# Odessa_Add_el.net
KiCad netlist of a schematic drawn in EAGLE
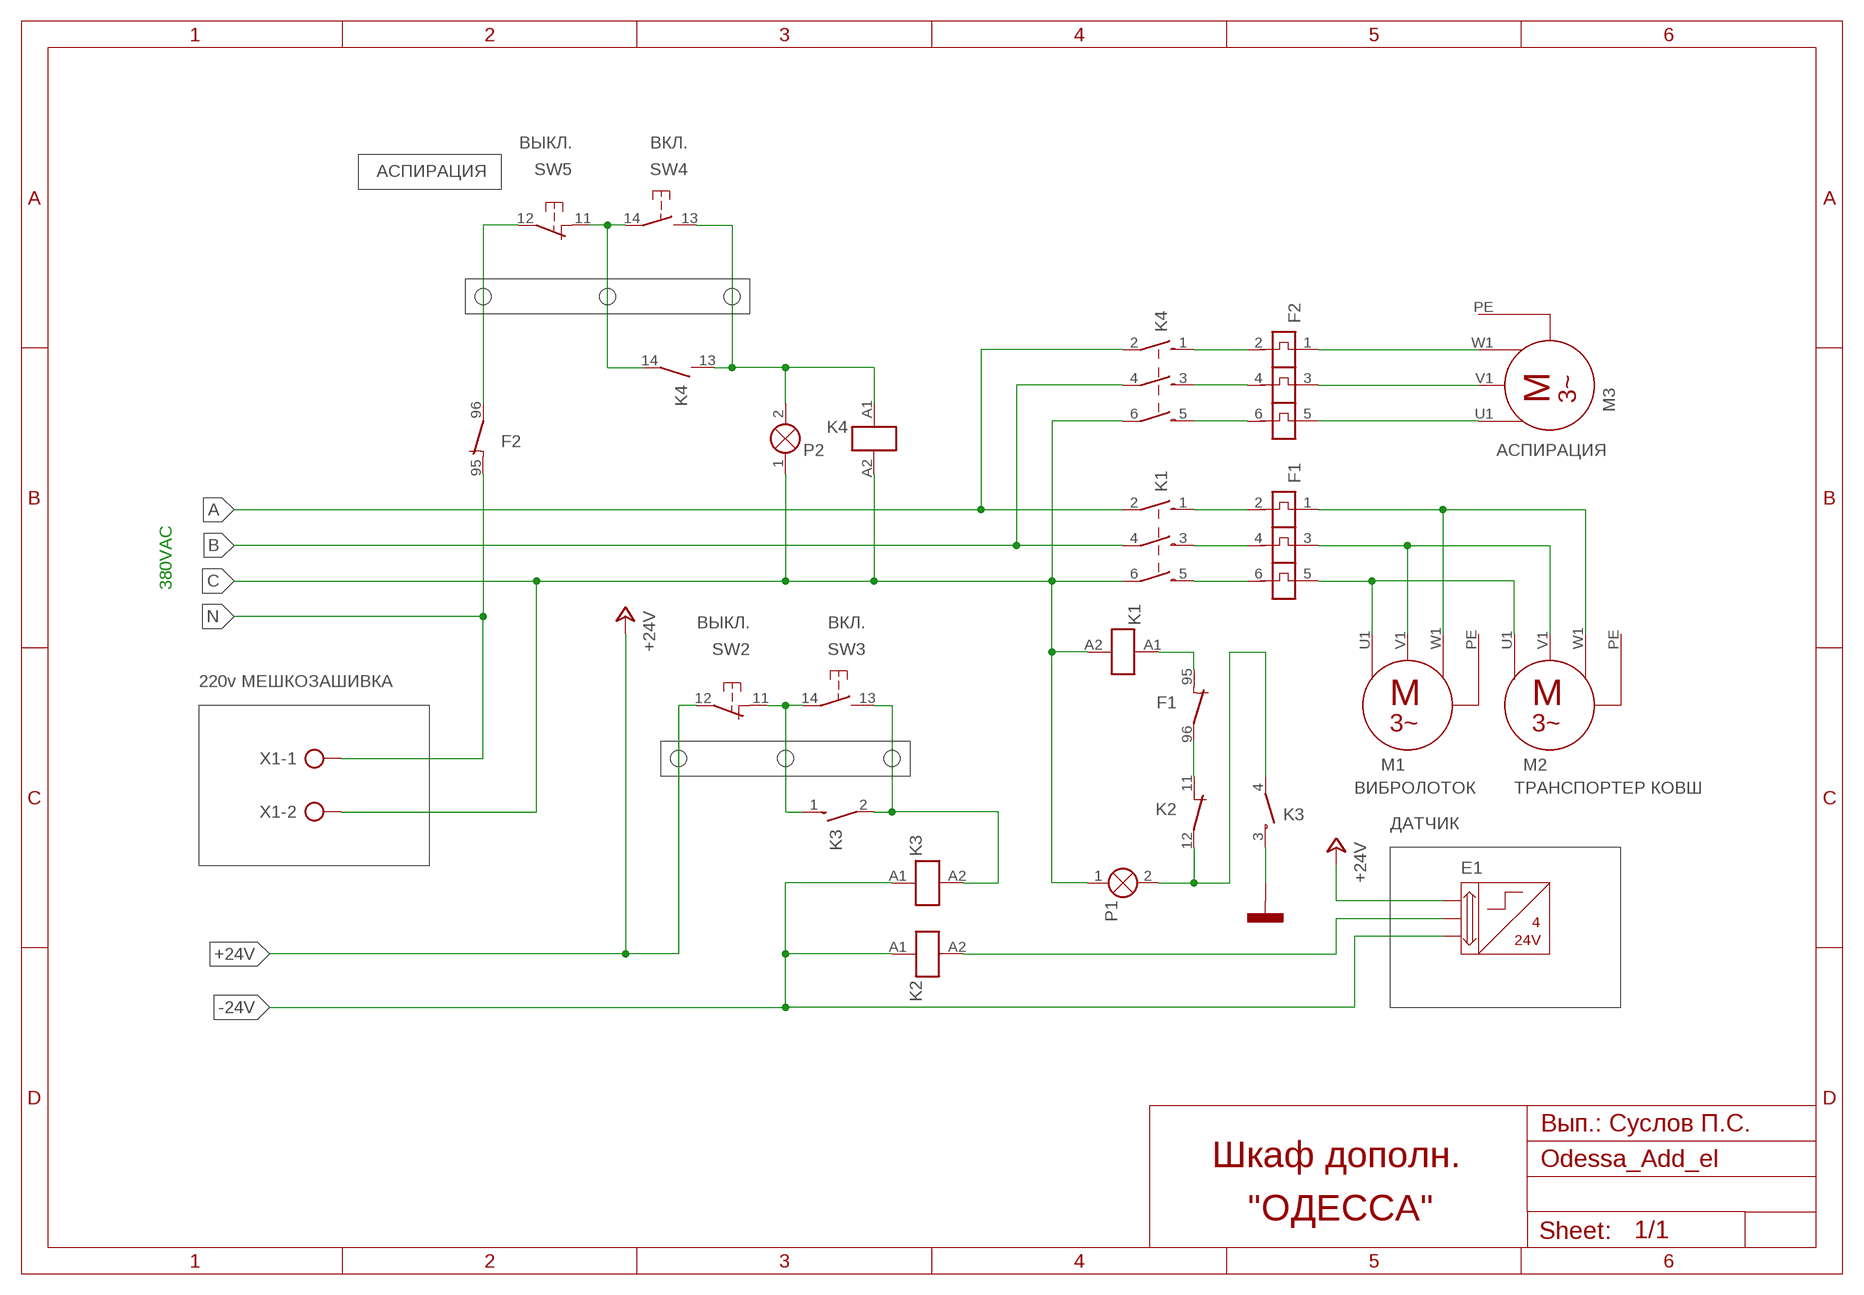
[diagram p0: schematic, sheet 1]

(export (version "E")
  (design (tool "Eeschema 10.0.6"))
  (components
    (comp (ref "E1")
      (value "6158EB")
      (footprint "eagle-import:6158EB")
      (libsource (lib "eagle-import") (part "6158EB"))
    )
    (comp (ref "F1")
      (value "MOTORSCHUTZSCHALTER_3-POL_THERM_AUSLOESUNG_HILFSKONTAKTE")
      (footprint "eagle-import:MOTORSCHUTZSCHALTER_3-POL_THERM_AUSLOESUNG_HILFSKONTAKT_95_96_97_98")
      (libsource (lib "eagle-import") (part "MOTORSCHUTZSCHALTER_3-POL_THERM_AUSLOESUNG_HILFSKONTAKTE"))
    )
    (comp (ref "F2")
      (value "MOTORSCHUTZSCHALTER_3-POL_THERM_AUSLOESUNG_HILFSKONTAKTE")
      (footprint "eagle-import:MOTORSCHUTZSCHALTER_3-POL_THERM_AUSLOESUNG_HILFSKONTAKT_95_96_97_98")
      (libsource (lib "eagle-import") (part "MOTORSCHUTZSCHALTER_3-POL_THERM_AUSLOESUNG_HILFSKONTAKTE"))
    )
    (comp (ref "K1")
      (value "HAUPTSCHUETZ_3-POL")
      (footprint "eagle-import:HAUPTSCHUETZ_3-POL")
      (libsource (lib "eagle-import") (part "HAUPTSCHUETZ_3-POL"))
    )
    (comp (ref "K2")
      (value "HILFSSCHUETZ_11-12")
      (footprint "eagle-import:HILFSSCHUETZ_11-12")
      (libsource (lib "eagle-import") (part "HILFSSCHUETZ_11-12"))
    )
    (comp (ref "K3")
      (value "HAUPTSCHUETZ_2-POL")
      (footprint "eagle-import:HAUPTSCHUETZ_2-POL")
      (libsource (lib "eagle-import") (part "HAUPTSCHUETZ_2-POL"))
    )
    (comp (ref "K4")
      (value "HAUPTSCHUETZ_3-POL_HILFSKONTAKT_13-14")
      (footprint "eagle-import:HAUPTSCHUETZ_3-POL+HILFSKONTAKT_13-14")
      (libsource (lib "eagle-import") (part "HAUPTSCHUETZ_3-POL_HILFSKONTAKT_13-14"))
    )
    (comp (ref "M1")
      (value "MOTOR_3-POL_PE")
      (footprint "eagle-import:MOTOR_3-POL_PE")
      (libsource (lib "eagle-import") (part "MOTOR_3-POL_PE"))
    )
    (comp (ref "M2")
      (value "MOTOR_3-POL_PE")
      (footprint "eagle-import:MOTOR_3-POL_PE")
      (libsource (lib "eagle-import") (part "MOTOR_3-POL_PE"))
    )
    (comp (ref "M3")
      (value "MOTOR_3-POL_PE")
      (footprint "eagle-import:MOTOR_3-POL_PE")
      (libsource (lib "eagle-import") (part "MOTOR_3-POL_PE"))
    )
    (comp (ref "P1")
      (value "SIGNALLAMPE")
      (footprint "eagle-import:LAMPE")
      (libsource (lib "eagle-import") (part "SIGNALLAMPE"))
    )
    (comp (ref "P2")
      (value "SIGNALLAMPE")
      (footprint "eagle-import:LAMPE")
      (libsource (lib "eagle-import") (part "SIGNALLAMPE"))
    )
    (comp (ref "SW2")
      (value "ВЫКЛ.")
      (footprint "eagle-import:OEFFNER_TASTSCHALTER")
      (libsource (lib "eagle-import") (part "OEFFNER_TASTSCHALTER"))
    )
    (comp (ref "SW3")
      (value "ВКЛ.")
      (footprint "eagle-import:SCHLIESSER_TASTSCHALTER")
      (libsource (lib "eagle-import") (part "SCHLIESSER_TASTSCHALTER"))
    )
    (comp (ref "SW4")
      (value "ВКЛ.")
      (footprint "eagle-import:SCHLIESSER_TASTSCHALTER")
      (libsource (lib "eagle-import") (part "SCHLIESSER_TASTSCHALTER"))
    )
    (comp (ref "SW5")
      (value "ВЫКЛ.")
      (footprint "eagle-import:OEFFNER_TASTSCHALTER")
      (libsource (lib "eagle-import") (part "OEFFNER_TASTSCHALTER"))
    )
    (comp (ref "X1")
      (value "AK500/2")
      (footprint "eagle-import:AK500_2")
      (libsource (lib "eagle-import") (part "AK500/2"))
    )
    (comp (ref "X4")
      (value "MASSE_ALLGEMEIN")
      (footprint "eagle-import:MASSE_ALLGEMEIN")
      (libsource (lib "eagle-import") (part "MASSE_ALLGEMEIN"))
    )
  )
  (nets
    (net (code "1") (name "+24V") (class "Default")
      (node (ref "SW2") (pin "12") (pinfunction "2_12") (pintype "input"))
    )
    (net (code "2") (name "-24V") (class "Default")
      (node (ref "K2") (pin "A1") (pinfunction "A1_A1") (pintype "input"))
      (node (ref "K3") (pin "A1") (pinfunction "A1_A1") (pintype "input"))
    )
    (net (code "3") (name "A") (class "Default")
      (node (ref "K1") (pin "2") (pinfunction "2_2") (pintype "passive"))
      (node (ref "K4") (pin "2") (pinfunction "2_2") (pintype "passive"))
    )
    (net (code "4") (name "B") (class "Default")
      (node (ref "K1") (pin "4") (pinfunction "4_4") (pintype "passive"))
      (node (ref "K4") (pin "4") (pinfunction "4_4") (pintype "passive"))
    )
    (net (code "5") (name "C") (class "Default")
      (node (ref "K1") (pin "6") (pinfunction "6_6") (pintype "passive"))
      (node (ref "K1") (pin "A2") (pinfunction "A2_A2") (pintype "input"))
      (node (ref "K4") (pin "6") (pinfunction "6_6") (pintype "passive"))
      (node (ref "K4") (pin "A2") (pinfunction "A2_A2") (pintype "input"))
      (node (ref "P1") (pin "1") (pinfunction "X1_1") (pintype "passive"))
      (node (ref "P2") (pin "1") (pinfunction "X1_1") (pintype "passive"))
      (node (ref "X1") (pin "2") (pinfunction "KL_2") (pintype "passive"))
    )
    (net (code "6") (name "N") (class "Default")
      (node (ref "F2") (pin "95") (pinfunction "95_95") (pintype "passive"))
      (node (ref "X1") (pin "1") (pinfunction "KL_1") (pintype "passive"))
    )
    (net (code "7") (name "Net-(E1-Pad1)") (class "Default")
      (node (ref "E1") (pin "1") (pinfunction "1_1") (pintype "passive"))
      (node (ref "K2") (pin "A2") (pinfunction "A2_A2") (pintype "input"))
    )
    (net (code "8") (name "Net-(F1-Pad1)") (class "Default")
      (node (ref "F1") (pin "1") (pinfunction "1_1") (pintype "passive"))
      (node (ref "M1") (pin "W1") (pinfunction "W1_W1") (pintype "passive"))
      (node (ref "M2") (pin "W1") (pinfunction "W1_W1") (pintype "passive"))
    )
    (net (code "9") (name "Net-(F1-Pad2)") (class "Default")
      (node (ref "F1") (pin "2") (pinfunction "2_2") (pintype "passive"))
      (node (ref "K1") (pin "1") (pinfunction "1_1") (pintype "passive"))
    )
    (net (code "10") (name "Net-(F1-Pad3)") (class "Default")
      (node (ref "F1") (pin "3") (pinfunction "3_3") (pintype "passive"))
      (node (ref "M1") (pin "V1") (pinfunction "V1_V1") (pintype "passive"))
      (node (ref "M2") (pin "V1") (pinfunction "V1_V1") (pintype "passive"))
    )
    (net (code "11") (name "Net-(F1-Pad4)") (class "Default")
      (node (ref "F1") (pin "4") (pinfunction "4_4") (pintype "passive"))
      (node (ref "K1") (pin "3") (pinfunction "3_3") (pintype "passive"))
    )
    (net (code "12") (name "Net-(F1-Pad5)") (class "Default")
      (node (ref "F1") (pin "5") (pinfunction "5_5") (pintype "passive"))
      (node (ref "M1") (pin "U1") (pinfunction "U1_U1") (pintype "passive"))
      (node (ref "M2") (pin "U1") (pinfunction "U1_U1") (pintype "passive"))
    )
    (net (code "13") (name "Net-(F1-Pad6)") (class "Default")
      (node (ref "F1") (pin "6") (pinfunction "6_6") (pintype "passive"))
      (node (ref "K1") (pin "5") (pinfunction "5_5") (pintype "passive"))
    )
    (net (code "14") (name "Net-(F1-Pad95)") (class "Default")
      (node (ref "F1") (pin "95") (pinfunction "95_95") (pintype "passive"))
      (node (ref "K1") (pin "A1") (pinfunction "A1_A1") (pintype "input"))
    )
    (net (code "15") (name "Net-(F2-Pad1)") (class "Default")
      (node (ref "F2") (pin "1") (pinfunction "1_1") (pintype "passive"))
      (node (ref "M3") (pin "W1") (pinfunction "W1_W1") (pintype "passive"))
    )
    (net (code "16") (name "Net-(F2-Pad2)") (class "Default")
      (node (ref "F2") (pin "2") (pinfunction "2_2") (pintype "passive"))
      (node (ref "K4") (pin "1") (pinfunction "1_1") (pintype "passive"))
    )
    (net (code "17") (name "Net-(F2-Pad3)") (class "Default")
      (node (ref "F2") (pin "3") (pinfunction "3_3") (pintype "passive"))
      (node (ref "M3") (pin "V1") (pinfunction "V1_V1") (pintype "passive"))
    )
    (net (code "18") (name "Net-(F2-Pad4)") (class "Default")
      (node (ref "F2") (pin "4") (pinfunction "4_4") (pintype "passive"))
      (node (ref "K4") (pin "3") (pinfunction "3_3") (pintype "passive"))
    )
    (net (code "19") (name "Net-(F2-Pad5)") (class "Default")
      (node (ref "F2") (pin "5") (pinfunction "5_5") (pintype "passive"))
      (node (ref "M3") (pin "U1") (pinfunction "U1_U1") (pintype "passive"))
    )
    (net (code "20") (name "Net-(F2-Pad6)") (class "Default")
      (node (ref "F2") (pin "6") (pinfunction "6_6") (pintype "passive"))
      (node (ref "K4") (pin "5") (pinfunction "5_5") (pintype "passive"))
    )
    (net (code "21") (name "Net-(K2A-1)") (class "Default")
      (node (ref "F1") (pin "96") (pinfunction "96_96") (pintype "passive"))
      (node (ref "K2") (pin "11") (pinfunction "1_11") (pintype "passive"))
    )
    (net (code "22") (name "Net-(K2A-2)") (class "Default")
      (node (ref "K2") (pin "12") (pinfunction "2_12") (pintype "passive"))
      (node (ref "K3") (pin "4") (pinfunction "4_4") (pintype "passive"))
      (node (ref "P1") (pin "2") (pinfunction "X2_2") (pintype "passive"))
    )
    (net (code "23") (name "Net-(K3B-3)") (class "Default")
      (node (ref "K3") (pin "1") (pinfunction "3_1") (pintype "passive"))
      (node (ref "SW2") (pin "11") (pinfunction "1_11") (pintype "input"))
      (node (ref "SW3") (pin "14") (pinfunction "4_14") (pintype "input"))
    )
    (net (code "24") (name "Net-(K3B-4)") (class "Default")
      (node (ref "K3") (pin "2") (pinfunction "4_2") (pintype "passive"))
      (node (ref "K3") (pin "A2") (pinfunction "A2_A2") (pintype "input"))
      (node (ref "SW3") (pin "13") (pinfunction "3_13") (pintype "input"))
    )
    (net (code "25") (name "Net-(K4B-3)") (class "Default")
      (node (ref "K4") (pin "13") (pinfunction "3_13") (pintype "passive"))
      (node (ref "K4") (pin "A1") (pinfunction "A1_A1") (pintype "input"))
      (node (ref "P2") (pin "2") (pinfunction "X2_2") (pintype "passive"))
      (node (ref "SW4") (pin "13") (pinfunction "3_13") (pintype "input"))
    )
    (net (code "26") (name "Net-(K4B-4)") (class "Default")
      (node (ref "K4") (pin "14") (pinfunction "4_14") (pintype "passive"))
      (node (ref "SW4") (pin "14") (pinfunction "4_14") (pintype "input"))
      (node (ref "SW5") (pin "11") (pinfunction "1_11") (pintype "input"))
    )
    (net (code "27") (name "Net-(SW5-2)") (class "Default")
      (node (ref "F2") (pin "96") (pinfunction "96_96") (pintype "passive"))
      (node (ref "SW5") (pin "12") (pinfunction "2_12") (pintype "input"))
    )
    (net (code "28") (name "Net-(X4-0V)") (class "Default")
      (node (ref "K3") (pin "3") (pinfunction "3_3") (pintype "passive"))
      (node (ref "X4") (pin "1") (pinfunction "0V_1") (pintype "passive"))
    )
    (net (code "29") (name "unconnected-(M1-PadPE)") (class "Default")
      (node (ref "M1") (pin "PE") (pinfunction "PE_PE") (pintype "passive"))
    )
    (net (code "30") (name "unconnected-(M2-PadPE)") (class "Default")
      (node (ref "M2") (pin "PE") (pinfunction "PE_PE") (pintype "passive"))
    )
    (net (code "31") (name "unconnected-(M3-PadPE)") (class "Default")
      (node (ref "M3") (pin "PE") (pinfunction "PE_PE") (pintype "passive"))
    )
  )
)
